# LOGIC_FPGA.net
KiCad netlist of a schematic drawn in Altium Designer
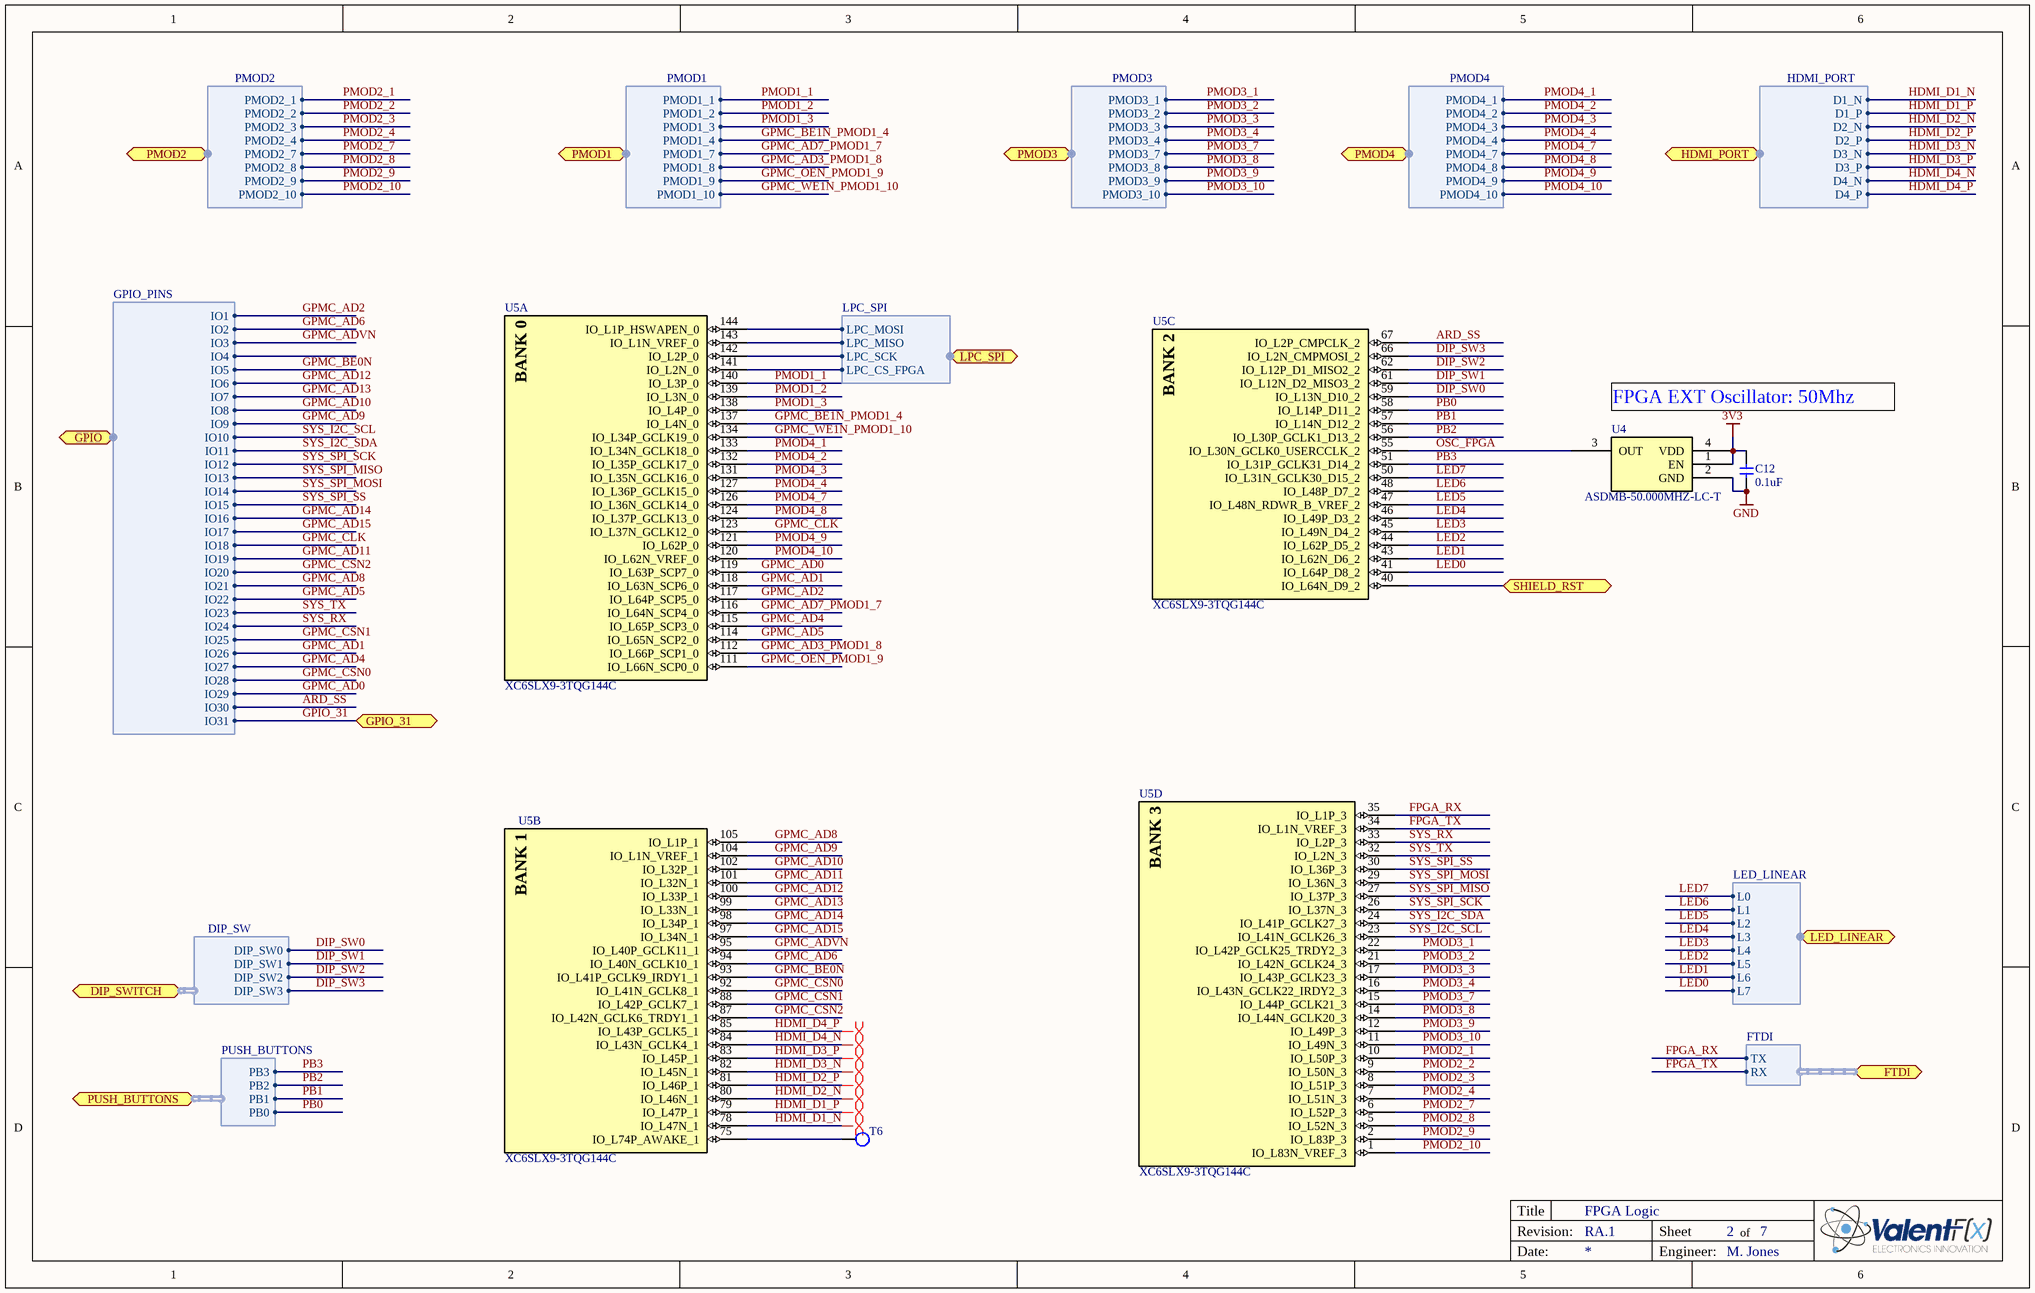
[diagram p0: LOGIC_FPGA.SchDoc]

(export (version "E")
  (design (tool "Eeschema 10.0.6"))
  (components
    (comp (ref "C12")
      (value "0.1uF")
      (footprint "C0603")
      (description "CAP CER .1UF 50V 10% X7R 0603")
      (fields
        (field (name "MANUFACTURER") "Murata Electronics North America")
        (field (name "MANUFACTURER PART NUMBER") "GRM188R71H104KA93D")
      )
      (libsource (lib "eCapacitors") (part "GRM188R71H104KA93D"))
    )
    (comp (ref "T6")
      (value "Test Point")
      (footprint "tp 18-28")
      (description "Test Point Smaller Symbol")
      (libsource (lib "mConnector") (part "Test Point 2"))
    )
    (comp (ref "U4")
      (value "ASDMB-50.000MHZ-LC-T")
      (footprint "ASDMB - osc")
      (description "OSC MEMS 50.000 MHZ SMD")
      (fields (field (name "MANUFACTURER") "Abracon Corporation"))
      (libsource (lib "eIC") (part "ASDMB-50.000MHZ-LC-T"))
    )
    (comp (ref "U5")
      (value "XC6SLX9-3TQG144C")
      (footprint "TQ144_L")
      (description "IC FPAG SPARTAN 6 9K 144TQFP")
      (fields (field (name "MANUFACTURER") "Xilinx Inc"))
      (libsource (lib "eIC") (part "XC6SLX9-3TQG144C"))
    )
  )
  (nets
    (net (code "12") (name "/ARD_SS") (class "Default")
      (node (ref "U5") (pin "67") (pinfunction "IO_L2P_CMPCLK_2_67") (pintype "bidirectional"))
    )
    (net (code "13") (name "/DIP_SW0") (class "Default")
      (node (ref "U5") (pin "59") (pinfunction "IO_L13N_D10_2_59") (pintype "bidirectional"))
    )
    (net (code "14") (name "/DIP_SW1") (class "Default")
      (node (ref "U5") (pin "61") (pinfunction "IO_L12N_D2_MISO3_2_61") (pintype "bidirectional"))
    )
    (net (code "15") (name "/DIP_SW2") (class "Default")
      (node (ref "U5") (pin "62") (pinfunction "IO_L12P_D1_MISO2_2_62") (pintype "bidirectional"))
    )
    (net (code "16") (name "/DIP_SW3") (class "Default")
      (node (ref "U5") (pin "66") (pinfunction "IO_L2N_CMPMOSI_2_66") (pintype "bidirectional"))
    )
    (net (code "17") (name "/FPGA_RX") (class "Default")
      (node (ref "U5") (pin "35") (pinfunction "IO_L1P_3_35") (pintype "bidirectional"))
    )
    (net (code "18") (name "/FPGA_TX") (class "Default")
      (node (ref "U5") (pin "34") (pinfunction "IO_L1N_VREF_3_34") (pintype "bidirectional"))
    )
    (net (code "20") (name "/GPMC_AD0") (class "Default")
      (node (ref "U5") (pin "119") (pinfunction "IO_L63P_SCP7_0_119") (pintype "bidirectional"))
    )
    (net (code "21") (name "/GPMC_AD1") (class "Default")
      (node (ref "U5") (pin "118") (pinfunction "IO_L63N_SCP6_0_118") (pintype "bidirectional"))
    )
    (net (code "22") (name "/GPMC_AD2") (class "Default")
      (node (ref "U5") (pin "117") (pinfunction "IO_L64P_SCP5_0_117") (pintype "bidirectional"))
    )
    (net (code "23") (name "/GPMC_AD3_PMOD1_8") (class "Default")
      (node (ref "U5") (pin "112") (pinfunction "IO_L66P_SCP1_0_112") (pintype "bidirectional"))
    )
    (net (code "24") (name "/GPMC_AD4") (class "Default")
      (node (ref "U5") (pin "115") (pinfunction "IO_L65P_SCP3_0_115") (pintype "bidirectional"))
    )
    (net (code "25") (name "/GPMC_AD5") (class "Default")
      (node (ref "U5") (pin "114") (pinfunction "IO_L65N_SCP2_0_114") (pintype "bidirectional"))
    )
    (net (code "26") (name "/GPMC_AD6") (class "Default")
      (node (ref "U5") (pin "94") (pinfunction "IO_L40N_GCLK10_1_94") (pintype "bidirectional"))
    )
    (net (code "27") (name "/GPMC_AD7_PMOD1_7") (class "Default")
      (node (ref "U5") (pin "116") (pinfunction "IO_L64N_SCP4_0_116") (pintype "bidirectional"))
    )
    (net (code "28") (name "/GPMC_AD8") (class "Default")
      (node (ref "U5") (pin "105") (pinfunction "IO_L1P_1_105") (pintype "bidirectional"))
    )
    (net (code "29") (name "/GPMC_AD9") (class "Default")
      (node (ref "U5") (pin "104") (pinfunction "IO_L1N_VREF_1_104") (pintype "bidirectional"))
    )
    (net (code "30") (name "/GPMC_AD10") (class "Default")
      (node (ref "U5") (pin "102") (pinfunction "IO_L32P_1_102") (pintype "bidirectional"))
    )
    (net (code "31") (name "/GPMC_AD11") (class "Default")
      (node (ref "U5") (pin "101") (pinfunction "IO_L32N_1_101") (pintype "bidirectional"))
    )
    (net (code "32") (name "/GPMC_AD12") (class "Default")
      (node (ref "U5") (pin "100") (pinfunction "IO_L33P_1_100") (pintype "bidirectional"))
    )
    (net (code "33") (name "/GPMC_AD13") (class "Default")
      (node (ref "U5") (pin "99") (pinfunction "IO_L33N_1_99") (pintype "bidirectional"))
    )
    (net (code "34") (name "/GPMC_AD14") (class "Default")
      (node (ref "U5") (pin "98") (pinfunction "IO_L34P_1_98") (pintype "bidirectional"))
    )
    (net (code "35") (name "/GPMC_AD15") (class "Default")
      (node (ref "U5") (pin "97") (pinfunction "IO_L34N_1_97") (pintype "bidirectional"))
    )
    (net (code "36") (name "/GPMC_ADVN") (class "Default")
      (node (ref "U5") (pin "95") (pinfunction "IO_L40P_GCLK11_1_95") (pintype "bidirectional"))
    )
    (net (code "37") (name "/GPMC_BE0N") (class "Default")
      (node (ref "U5") (pin "93") (pinfunction "IO_L41P_GCLK9_IRDY1_1_93") (pintype "bidirectional"))
    )
    (net (code "38") (name "/GPMC_BE1N_PMOD1_4") (class "Default")
      (node (ref "U5") (pin "137") (pinfunction "IO_L4N_0_137") (pintype "bidirectional"))
    )
    (net (code "39") (name "/GPMC_CLK") (class "Default")
      (node (ref "U5") (pin "123") (pinfunction "IO_L37N_GCLK12_0_123") (pintype "bidirectional"))
    )
    (net (code "40") (name "/GPMC_CSN0") (class "Default")
      (node (ref "U5") (pin "92") (pinfunction "IO_L41N_GCLK8_1_92") (pintype "bidirectional"))
    )
    (net (code "41") (name "/GPMC_CSN1") (class "Default")
      (node (ref "U5") (pin "88") (pinfunction "IO_L42P_GCLK7_1_88") (pintype "bidirectional"))
    )
    (net (code "42") (name "/GPMC_CSN2") (class "Default")
      (node (ref "U5") (pin "87") (pinfunction "IO_L42N_GCLK6_TRDY1_1_87") (pintype "bidirectional"))
    )
    (net (code "43") (name "/GPMC_OEN_PMOD1_9") (class "Default")
      (node (ref "U5") (pin "111") (pinfunction "IO_L66N_SCP0_0_111") (pintype "bidirectional"))
    )
    (net (code "44") (name "/GPMC_WE1N_PMOD1_10") (class "Default")
      (node (ref "U5") (pin "134") (pinfunction "IO_L34P_GCLK19_0_134") (pintype "bidirectional"))
    )
    (net (code "45") (name "/HDMI_D1_N") (class "Default")
      (node (ref "U5") (pin "78") (pinfunction "IO_L47N_1_78") (pintype "bidirectional"))
    )
    (net (code "46") (name "/HDMI_D1_P") (class "Default")
      (node (ref "U5") (pin "79") (pinfunction "IO_L47P_1_79") (pintype "bidirectional"))
    )
    (net (code "47") (name "/HDMI_D2_N") (class "Default")
      (node (ref "U5") (pin "80") (pinfunction "IO_L46N_1_80") (pintype "bidirectional"))
    )
    (net (code "48") (name "/HDMI_D2_P") (class "Default")
      (node (ref "U5") (pin "81") (pinfunction "IO_L46P_1_81") (pintype "bidirectional"))
    )
    (net (code "49") (name "/HDMI_D3_N") (class "Default")
      (node (ref "U5") (pin "82") (pinfunction "IO_L45N_1_82") (pintype "bidirectional"))
    )
    (net (code "50") (name "/HDMI_D3_P") (class "Default")
      (node (ref "U5") (pin "83") (pinfunction "IO_L45P_1_83") (pintype "bidirectional"))
    )
    (net (code "51") (name "/HDMI_D4_N") (class "Default")
      (node (ref "U5") (pin "84") (pinfunction "IO_L43N_GCLK4_1_84") (pintype "bidirectional"))
    )
    (net (code "52") (name "/HDMI_D4_P") (class "Default")
      (node (ref "U5") (pin "85") (pinfunction "IO_L43P_GCLK5_1_85") (pintype "bidirectional"))
    )
    (net (code "54") (name "/LED0") (class "Default")
      (node (ref "U5") (pin "41") (pinfunction "IO_L64P_D8_2_41") (pintype "bidirectional"))
    )
    (net (code "55") (name "/LED1") (class "Default")
      (node (ref "U5") (pin "43") (pinfunction "IO_L62N_D6_2_43") (pintype "bidirectional"))
    )
    (net (code "56") (name "/LED2") (class "Default")
      (node (ref "U5") (pin "44") (pinfunction "IO_L62P_D5_2_44") (pintype "bidirectional"))
    )
    (net (code "57") (name "/LED3") (class "Default")
      (node (ref "U5") (pin "45") (pinfunction "IO_L49N_D4_2_45") (pintype "bidirectional"))
    )
    (net (code "58") (name "/LED4") (class "Default")
      (node (ref "U5") (pin "46") (pinfunction "IO_L49P_D3_2_46") (pintype "bidirectional"))
    )
    (net (code "59") (name "/LED5") (class "Default")
      (node (ref "U5") (pin "47") (pinfunction "IO_L48N_RDWR_B_VREF_2_47") (pintype "bidirectional"))
    )
    (net (code "60") (name "/LED6") (class "Default")
      (node (ref "U5") (pin "48") (pinfunction "IO_L48P_D7_2_48") (pintype "bidirectional"))
    )
    (net (code "61") (name "/LED7") (class "Default")
      (node (ref "U5") (pin "50") (pinfunction "IO_L31N_GCLK30_D15_2_50") (pintype "bidirectional"))
    )
    (net (code "62") (name "/LPC_CS_FPGA") (class "Default")
      (node (ref "U5") (pin "141") (pinfunction "IO_L2N_0_141") (pintype "bidirectional"))
    )
    (net (code "63") (name "/LPC_MISO") (class "Default")
      (node (ref "U5") (pin "143") (pinfunction "IO_L1N_VREF_0_143") (pintype "bidirectional"))
    )
    (net (code "64") (name "/LPC_MOSI") (class "Default")
      (node (ref "U5") (pin "144") (pinfunction "IO_L1P_HSWAPEN_0_144") (pintype "bidirectional"))
    )
    (net (code "65") (name "/LPC_SCK") (class "Default")
      (node (ref "U5") (pin "142") (pinfunction "IO_L2P_0_142") (pintype "bidirectional"))
    )
    (net (code "66") (name "/OSC_FPGA") (class "Default")
      (node (ref "U4") (pin "3") (pinfunction "OUT_3") (pintype "passive"))
      (node (ref "U5") (pin "55") (pinfunction "IO_L30N_GCLK0_USERCCLK_2_55") (pintype "bidirectional"))
    )
    (net (code "67") (name "/PB0") (class "Default")
      (node (ref "U5") (pin "58") (pinfunction "IO_L14P_D11_2_58") (pintype "bidirectional"))
    )
    (net (code "68") (name "/PB1") (class "Default")
      (node (ref "U5") (pin "57") (pinfunction "IO_L14N_D12_2_57") (pintype "bidirectional"))
    )
    (net (code "69") (name "/PB2") (class "Default")
      (node (ref "U5") (pin "56") (pinfunction "IO_L30P_GCLK1_D13_2_56") (pintype "bidirectional"))
    )
    (net (code "70") (name "/PB3") (class "Default")
      (node (ref "U5") (pin "51") (pinfunction "IO_L31P_GCLK31_D14_2_51") (pintype "bidirectional"))
    )
    (net (code "71") (name "/PMOD1_1") (class "Default")
      (node (ref "U5") (pin "140") (pinfunction "IO_L3P_0_140") (pintype "bidirectional"))
    )
    (net (code "72") (name "/PMOD1_2") (class "Default")
      (node (ref "U5") (pin "139") (pinfunction "IO_L3N_0_139") (pintype "bidirectional"))
    )
    (net (code "73") (name "/PMOD1_3") (class "Default")
      (node (ref "U5") (pin "138") (pinfunction "IO_L4P_0_138") (pintype "bidirectional"))
    )
    (net (code "74") (name "/PMOD2_1") (class "Default")
      (node (ref "U5") (pin "10") (pinfunction "IO_L50P_3_10") (pintype "bidirectional"))
    )
    (net (code "75") (name "/PMOD2_2") (class "Default")
      (node (ref "U5") (pin "9") (pinfunction "IO_L50N_3_9") (pintype "bidirectional"))
    )
    (net (code "76") (name "/PMOD2_3") (class "Default")
      (node (ref "U5") (pin "8") (pinfunction "IO_L51P_3_8") (pintype "bidirectional"))
    )
    (net (code "77") (name "/PMOD2_4") (class "Default")
      (node (ref "U5") (pin "7") (pinfunction "IO_L51N_3_7") (pintype "bidirectional"))
    )
    (net (code "78") (name "/PMOD2_7") (class "Default")
      (node (ref "U5") (pin "6") (pinfunction "IO_L52P_3_6") (pintype "bidirectional"))
    )
    (net (code "79") (name "/PMOD2_8") (class "Default")
      (node (ref "U5") (pin "5") (pinfunction "IO_L52N_3_5") (pintype "bidirectional"))
    )
    (net (code "80") (name "/PMOD2_9") (class "Default")
      (node (ref "U5") (pin "2") (pinfunction "IO_L83P_3_2") (pintype "bidirectional"))
    )
    (net (code "81") (name "/PMOD2_10") (class "Default")
      (node (ref "U5") (pin "1") (pinfunction "IO_L83N_VREF_3_1") (pintype "bidirectional"))
    )
    (net (code "82") (name "/PMOD3_1") (class "Default")
      (node (ref "U5") (pin "22") (pinfunction "IO_L42P_GCLK25_TRDY2_3_22") (pintype "bidirectional"))
    )
    (net (code "83") (name "/PMOD3_2") (class "Default")
      (node (ref "U5") (pin "21") (pinfunction "IO_L42N_GCLK24_3_21") (pintype "bidirectional"))
    )
    (net (code "84") (name "/PMOD3_3") (class "Default")
      (node (ref "U5") (pin "17") (pinfunction "IO_L43P_GCLK23_3_17") (pintype "bidirectional"))
    )
    (net (code "85") (name "/PMOD3_4") (class "Default")
      (node (ref "U5") (pin "16") (pinfunction "IO_L43N_GCLK22_IRDY2_3_16") (pintype "bidirectional"))
    )
    (net (code "86") (name "/PMOD3_7") (class "Default")
      (node (ref "U5") (pin "15") (pinfunction "IO_L44P_GCLK21_3_15") (pintype "bidirectional"))
    )
    (net (code "87") (name "/PMOD3_8") (class "Default")
      (node (ref "U5") (pin "14") (pinfunction "IO_L44N_GCLK20_3_14") (pintype "bidirectional"))
    )
    (net (code "88") (name "/PMOD3_9") (class "Default")
      (node (ref "U5") (pin "12") (pinfunction "IO_L49P_3_12") (pintype "bidirectional"))
    )
    (net (code "89") (name "/PMOD3_10") (class "Default")
      (node (ref "U5") (pin "11") (pinfunction "IO_L49N_3_11") (pintype "bidirectional"))
    )
    (net (code "90") (name "/PMOD4_1") (class "Default")
      (node (ref "U5") (pin "133") (pinfunction "IO_L34N_GCLK18_0_133") (pintype "bidirectional"))
    )
    (net (code "91") (name "/PMOD4_2") (class "Default")
      (node (ref "U5") (pin "132") (pinfunction "IO_L35P_GCLK17_0_132") (pintype "bidirectional"))
    )
    (net (code "92") (name "/PMOD4_3") (class "Default")
      (node (ref "U5") (pin "131") (pinfunction "IO_L35N_GCLK16_0_131") (pintype "bidirectional"))
    )
    (net (code "93") (name "/PMOD4_4") (class "Default")
      (node (ref "U5") (pin "127") (pinfunction "IO_L36P_GCLK15_0_127") (pintype "bidirectional"))
    )
    (net (code "94") (name "/PMOD4_7") (class "Default")
      (node (ref "U5") (pin "126") (pinfunction "IO_L36N_GCLK14_0_126") (pintype "bidirectional"))
    )
    (net (code "95") (name "/PMOD4_8") (class "Default")
      (node (ref "U5") (pin "124") (pinfunction "IO_L37P_GCLK13_0_124") (pintype "bidirectional"))
    )
    (net (code "96") (name "/PMOD4_9") (class "Default")
      (node (ref "U5") (pin "121") (pinfunction "IO_L62P_0_121") (pintype "bidirectional"))
    )
    (net (code "97") (name "/PMOD4_10") (class "Default")
      (node (ref "U5") (pin "120") (pinfunction "IO_L62N_VREF_0_120") (pintype "bidirectional"))
    )
    (net (code "98") (name "/SHIELD_RST") (class "Default")
      (node (ref "U5") (pin "40") (pinfunction "IO_L64N_D9_2_40") (pintype "bidirectional"))
    )
    (net (code "99") (name "/SYS_I2C_SCL") (class "Default")
      (node (ref "U5") (pin "23") (pinfunction "IO_L41N_GCLK26_3_23") (pintype "bidirectional"))
    )
    (net (code "100") (name "/SYS_I2C_SDA") (class "Default")
      (node (ref "U5") (pin "24") (pinfunction "IO_L41P_GCLK27_3_24") (pintype "bidirectional"))
    )
    (net (code "101") (name "/SYS_RX") (class "Default")
      (node (ref "U5") (pin "33") (pinfunction "IO_L2P_3_33") (pintype "bidirectional"))
    )
    (net (code "102") (name "/SYS_SPI_MISO") (class "Default")
      (node (ref "U5") (pin "27") (pinfunction "IO_L37P_3_27") (pintype "bidirectional"))
    )
    (net (code "103") (name "/SYS_SPI_MOSI") (class "Default")
      (node (ref "U5") (pin "29") (pinfunction "IO_L36N_3_29") (pintype "bidirectional"))
    )
    (net (code "104") (name "/SYS_SPI_SCK") (class "Default")
      (node (ref "U5") (pin "26") (pinfunction "IO_L37N_3_26") (pintype "bidirectional"))
    )
    (net (code "105") (name "/SYS_SPI_SS") (class "Default")
      (node (ref "U5") (pin "30") (pinfunction "IO_L36P_3_30") (pintype "bidirectional"))
    )
    (net (code "106") (name "/SYS_TX") (class "Default")
      (node (ref "U5") (pin "32") (pinfunction "IO_L2N_3_32") (pintype "bidirectional"))
    )
    (net (code "118") (name "3V3") (class "Default")
      (node (ref "C12") (pin "2") (pinfunction "2_2") (pintype "passive"))
      (node (ref "U4") (pin "1") (pinfunction "EN_1") (pintype "passive"))
      (node (ref "U4") (pin "4") (pinfunction "VDD_4") (pintype "passive"))
    )
    (net (code "119") (name "GND") (class "Default")
      (node (ref "C12") (pin "1") (pinfunction "1_1") (pintype "passive"))
      (node (ref "U4") (pin "2") (pinfunction "GND_2") (pintype "passive"))
    )
    (net (code "120") (name "Net-(U5B-IO_L74P_AWAKE_1)") (class "Default")
      (node (ref "T6") (pin "1") (pinfunction "1_1") (pintype "passive"))
      (node (ref "U5") (pin "75") (pinfunction "IO_L74P_AWAKE_1_75") (pintype "bidirectional"))
    )
  )
)
